# digispark_shield_led_matrix.net
KiCad netlist of a schematic drawn in EAGLE
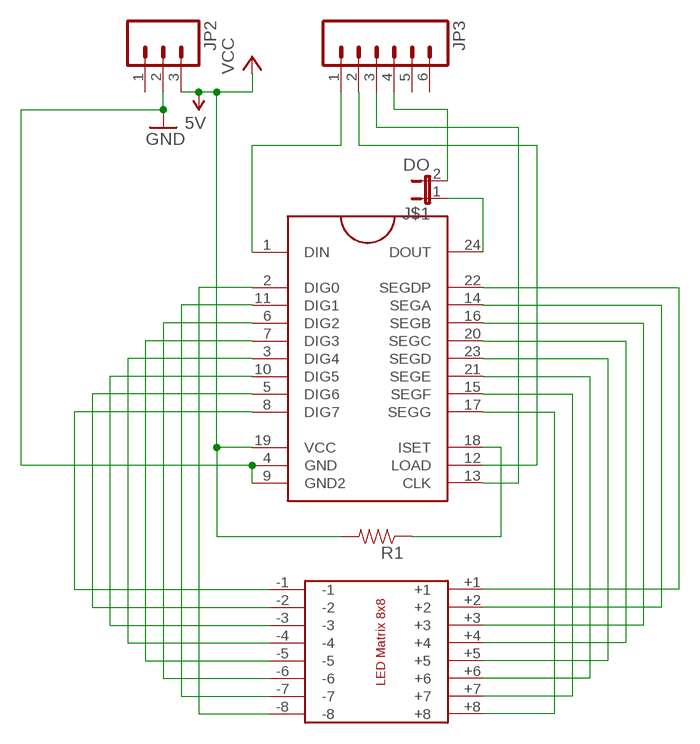
[diagram p0: schematic, sheet 1]

(export (version "E")
  (design (tool "Eeschema 10.0.6"))
  (components
    (comp (ref "J$1")
      (value "DO")
      (footprint "eagle-import:SJ_2S-NO")
      (libsource (lib "eagle-import") (part "JUMPER-2SMD-NO"))
    )
    (comp (ref "JP2")
      (value "M03PTH")
      (footprint "eagle-import:1X03")
      (libsource (lib "eagle-import") (part "M03PTH"))
    )
    (comp (ref "JP3")
      (value "M06SIP")
      (footprint "eagle-import:1X06")
      (libsource (lib "eagle-import") (part "M06SIP"))
    )
    (comp (ref "R1")
      (value "RESISTORAXIAL-0.3")
      (footprint "eagle-import:AXIAL-0.3")
      (libsource (lib "eagle-import") (part "RESISTORAXIAL-0.3"))
    )
    (comp (ref "U$1")
      (value "LED_ARRAY_8X8")
      (footprint "eagle-import:LED_8X8_2MM_BL-M07C881")
      (libsource (lib "eagle-import") (part "LED_ARRAY_8X8"))
    )
    (comp (ref "U$2")
      (value "MAX7219")
      (footprint "eagle-import:SO-24W")
      (libsource (lib "eagle-import") (part "MAX7219"))
    )
  )
  (nets
    (net (code "1") (name "5V") (class "Default")
      (node (ref "JP2") (pin "3") (pinfunction "3_3") (pintype "passive"))
      (node (ref "R1") (pin "P$2") (pinfunction "2_P$2") (pintype "passive"))
      (node (ref "U$2") (pin "19") (pinfunction "VCC_19") (pintype "bidirectional"))
    )
    (net (code "2") (name "GND") (class "Default")
      (node (ref "JP2") (pin "2") (pinfunction "2_2") (pintype "passive"))
      (node (ref "U$2") (pin "4") (pinfunction "GND_4") (pintype "bidirectional"))
      (node (ref "U$2") (pin "9") (pinfunction "GND2_9") (pintype "bidirectional"))
    )
    (net (code "3") (name "Net-(J$1-Pad2)") (class "Default")
      (node (ref "J$1") (pin "2") (pinfunction "2_2") (pintype "passive"))
      (node (ref "JP3") (pin "4") (pinfunction "4_4") (pintype "passive"))
    )
    (net (code "4") (name "Net-(R1-1)") (class "Default")
      (node (ref "R1") (pin "P$1") (pinfunction "1_P$1") (pintype "passive"))
      (node (ref "U$2") (pin "18") (pinfunction "ISET_18") (pintype "bidirectional"))
    )
    (net (code "5") (name "Net-(U$2-CLK)") (class "Default")
      (node (ref "JP3") (pin "3") (pinfunction "3_3") (pintype "passive"))
      (node (ref "U$2") (pin "13") (pinfunction "CLK_13") (pintype "bidirectional"))
    )
    (net (code "6") (name "Net-(U$2-DIG0)") (class "Default")
      (node (ref "U$1") (pin "-8") (pinfunction "-8_-8") (pintype "bidirectional"))
      (node (ref "U$2") (pin "2") (pinfunction "DIG0_2") (pintype "bidirectional"))
    )
    (net (code "7") (name "Net-(U$2-DIG1)") (class "Default")
      (node (ref "U$1") (pin "-7") (pinfunction "-7_-7") (pintype "bidirectional"))
      (node (ref "U$2") (pin "11") (pinfunction "DIG1_11") (pintype "bidirectional"))
    )
    (net (code "8") (name "Net-(U$2-DIG2)") (class "Default")
      (node (ref "U$1") (pin "-6") (pinfunction "-6_-6") (pintype "bidirectional"))
      (node (ref "U$2") (pin "6") (pinfunction "DIG2_6") (pintype "bidirectional"))
    )
    (net (code "9") (name "Net-(U$2-DIG3)") (class "Default")
      (node (ref "U$1") (pin "-5") (pinfunction "-5_-5") (pintype "bidirectional"))
      (node (ref "U$2") (pin "7") (pinfunction "DIG3_7") (pintype "bidirectional"))
    )
    (net (code "10") (name "Net-(U$2-DIG4)") (class "Default")
      (node (ref "U$1") (pin "-4") (pinfunction "-4_-4") (pintype "bidirectional"))
      (node (ref "U$2") (pin "3") (pinfunction "DIG4_3") (pintype "bidirectional"))
    )
    (net (code "11") (name "Net-(U$2-DIG5)") (class "Default")
      (node (ref "U$1") (pin "-3") (pinfunction "-3_-3") (pintype "bidirectional"))
      (node (ref "U$2") (pin "10") (pinfunction "DIG5_10") (pintype "bidirectional"))
    )
    (net (code "12") (name "Net-(U$2-DIG6)") (class "Default")
      (node (ref "U$1") (pin "-2") (pinfunction "-2_-2") (pintype "bidirectional"))
      (node (ref "U$2") (pin "5") (pinfunction "DIG6_5") (pintype "bidirectional"))
    )
    (net (code "13") (name "Net-(U$2-DIG7)") (class "Default")
      (node (ref "U$1") (pin "-1") (pinfunction "-1_-1") (pintype "bidirectional"))
      (node (ref "U$2") (pin "8") (pinfunction "DIG7_8") (pintype "bidirectional"))
    )
    (net (code "14") (name "Net-(U$2-DIN)") (class "Default")
      (node (ref "JP3") (pin "1") (pinfunction "1_1") (pintype "passive"))
      (node (ref "U$2") (pin "1") (pinfunction "DIN_1") (pintype "bidirectional"))
    )
    (net (code "15") (name "Net-(U$2-DOUT)") (class "Default")
      (node (ref "J$1") (pin "1") (pinfunction "1_1") (pintype "passive"))
      (node (ref "U$2") (pin "24") (pinfunction "DOUT_24") (pintype "bidirectional"))
    )
    (net (code "16") (name "Net-(U$2-LOAD)") (class "Default")
      (node (ref "JP3") (pin "2") (pinfunction "2_2") (pintype "passive"))
      (node (ref "U$2") (pin "12") (pinfunction "LOAD_12") (pintype "bidirectional"))
    )
    (net (code "17") (name "Net-(U$2-SEGA)") (class "Default")
      (node (ref "U$1") (pin "+2") (pinfunction "+2_+2") (pintype "bidirectional"))
      (node (ref "U$2") (pin "14") (pinfunction "SEGA_14") (pintype "bidirectional"))
    )
    (net (code "18") (name "Net-(U$2-SEGB)") (class "Default")
      (node (ref "U$1") (pin "+3") (pinfunction "+3_+3") (pintype "bidirectional"))
      (node (ref "U$2") (pin "16") (pinfunction "SEGB_16") (pintype "bidirectional"))
    )
    (net (code "19") (name "Net-(U$2-SEGC)") (class "Default")
      (node (ref "U$1") (pin "+4") (pinfunction "+4_+4") (pintype "bidirectional"))
      (node (ref "U$2") (pin "20") (pinfunction "SEGC_20") (pintype "bidirectional"))
    )
    (net (code "20") (name "Net-(U$2-SEGD)") (class "Default")
      (node (ref "U$1") (pin "+5") (pinfunction "+5_+5") (pintype "bidirectional"))
      (node (ref "U$2") (pin "23") (pinfunction "SEGD_23") (pintype "bidirectional"))
    )
    (net (code "21") (name "Net-(U$2-SEGDP)") (class "Default")
      (node (ref "U$1") (pin "+1") (pinfunction "+1_+1") (pintype "bidirectional"))
      (node (ref "U$2") (pin "22") (pinfunction "SEGDP_22") (pintype "bidirectional"))
    )
    (net (code "22") (name "Net-(U$2-SEGE)") (class "Default")
      (node (ref "U$1") (pin "+6") (pinfunction "+6_+6") (pintype "bidirectional"))
      (node (ref "U$2") (pin "21") (pinfunction "SEGE_21") (pintype "bidirectional"))
    )
    (net (code "23") (name "Net-(U$2-SEGF)") (class "Default")
      (node (ref "U$1") (pin "+7") (pinfunction "+7_+7") (pintype "bidirectional"))
      (node (ref "U$2") (pin "15") (pinfunction "SEGF_15") (pintype "bidirectional"))
    )
    (net (code "24") (name "Net-(U$2-SEGG)") (class "Default")
      (node (ref "U$1") (pin "+8") (pinfunction "+8_+8") (pintype "bidirectional"))
      (node (ref "U$2") (pin "17") (pinfunction "SEGG_17") (pintype "bidirectional"))
    )
    (net (code "25") (name "unconnected-(JP2-Pad1)") (class "Default")
      (node (ref "JP2") (pin "1") (pinfunction "1_1") (pintype "passive"))
    )
    (net (code "26") (name "unconnected-(JP3-Pad5)") (class "Default")
      (node (ref "JP3") (pin "5") (pinfunction "5_5") (pintype "passive"))
    )
    (net (code "27") (name "unconnected-(JP3-Pad6)") (class "Default")
      (node (ref "JP3") (pin "6") (pinfunction "6_6") (pintype "passive"))
    )
  )
)
